# CAN_Bus_Controller_-_REV_1.net
KiCad netlist of a schematic drawn in EAGLE
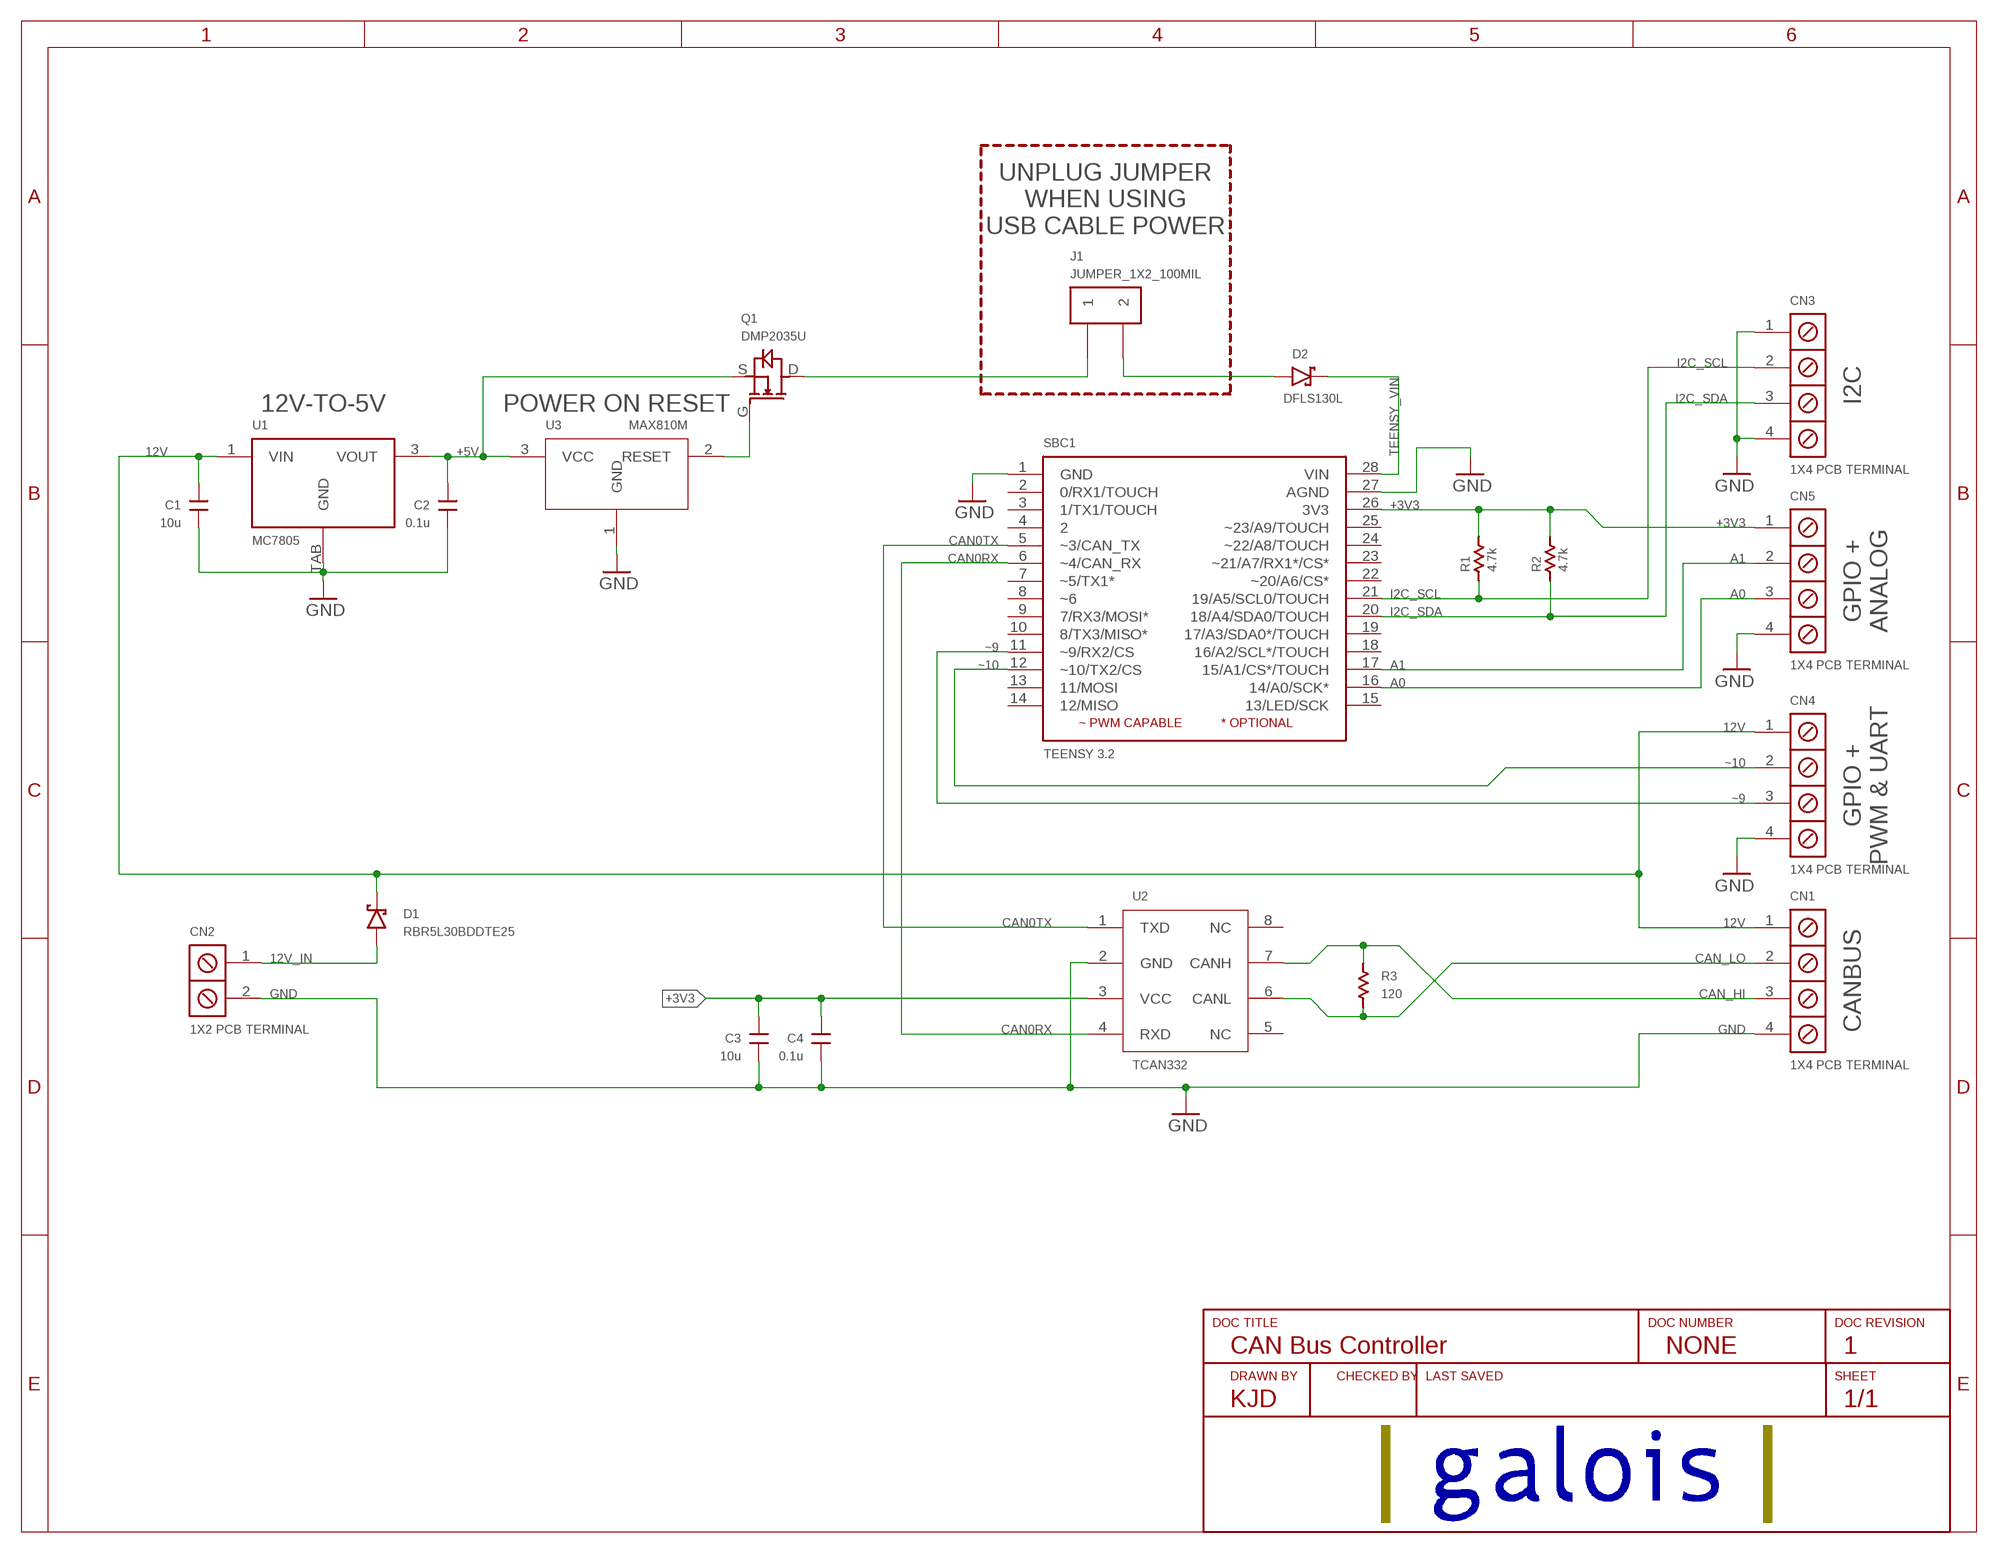
[diagram p0: schematic, sheet 1]

(export (version "E")
  (design (tool "Eeschema 10.0.6"))
  (components
    (comp (ref "C1")
      (value "10u")
      (footprint "eagle-import:EIA1206")
      (fields (field (name "MPN") "CL31A106KBHNNNE"))
      (libsource (lib "eagle-import") (part "C_SMDC1206"))
    )
    (comp (ref "C2")
      (value "0.1u")
      (footprint "eagle-import:EIA0603")
      (fields (field (name "MPN") "CL10B104KA8NNNC"))
      (libsource (lib "eagle-import") (part "C_SMDC0603"))
    )
    (comp (ref "C3")
      (value "10u")
      (footprint "eagle-import:EIA1206")
      (fields (field (name "MPN") "CL31A106KBHNNNE"))
      (libsource (lib "eagle-import") (part "C_SMDC1206"))
    )
    (comp (ref "C4")
      (value "0.1u")
      (footprint "eagle-import:EIA0603")
      (fields (field (name "MPN") "CL10B104KA8NNNC"))
      (libsource (lib "eagle-import") (part "C_SMDC0603"))
    )
    (comp (ref "CN1")
      (value "1X4 PCB TERMINAL")
      (footprint "eagle-import:PCB_TERM_3.5MM_PITCH_1X4")
      (fields (field (name "MPN") "1984633"))
      (libsource (lib "eagle-import") (part "1984633"))
    )
    (comp (ref "CN2")
      (value "1X2 PCB TERMINAL")
      (footprint "eagle-import:PCB_TERM_3.5MM_PITCH_1X2")
      (fields (field (name "MPN") "1984617"))
      (libsource (lib "eagle-import") (part "1984617"))
    )
    (comp (ref "CN3")
      (value "1X4 PCB TERMINAL")
      (footprint "eagle-import:PCB_TERM_3.5MM_PITCH_1X4")
      (fields (field (name "MPN") "1984633"))
      (libsource (lib "eagle-import") (part "1984633"))
    )
    (comp (ref "CN4")
      (value "1X4 PCB TERMINAL")
      (footprint "eagle-import:PCB_TERM_3.5MM_PITCH_1X4")
      (fields (field (name "MPN") "1984633"))
      (libsource (lib "eagle-import") (part "1984633"))
    )
    (comp (ref "CN5")
      (value "1X4 PCB TERMINAL")
      (footprint "eagle-import:PCB_TERM_3.5MM_PITCH_1X4")
      (fields (field (name "MPN") "1984633"))
      (libsource (lib "eagle-import") (part "1984633"))
    )
    (comp (ref "D1")
      (value "RBR5L30BDDTE25")
      (footprint "eagle-import:SMA")
      (fields (field (name "MPN") "RBR5L30BDDTE25"))
      (libsource (lib "eagle-import") (part "SCHOTTKYSMA"))
    )
    (comp (ref "D2")
      (value "DFLS130L")
      (footprint "eagle-import:POWERDI_123")
      (fields (field (name "MPN") "DFLS130L-7"))
      (libsource (lib "eagle-import") (part "SCHOTTKYPOWERDI_123"))
    )
    (comp (ref "J1")
      (value "JUMPER_1X2_100MIL")
      (footprint "eagle-import:1X2_100MIL_THRU")
      (fields (field (name "MPN") "QPC02SXGN-RC"))
      (libsource (lib "eagle-import") (part "1X2"))
    )
    (comp (ref "Q1")
      (value "DMP2035U")
      (footprint "eagle-import:SOT-23-3")
      (fields (field (name "MPN") "DMP2035U-7"))
      (libsource (lib "eagle-import") (part "DMP2035U"))
    )
    (comp (ref "R1")
      (value "4.7k")
      (footprint "eagle-import:EIA0603")
      (fields (field (name "MPN") "ERJ-3EKF4701V"))
      (libsource (lib "eagle-import") (part "R_SMDR0603"))
    )
    (comp (ref "R2")
      (value "4.7k")
      (footprint "eagle-import:EIA0603")
      (fields (field (name "MPN") "ERJ-3EKF4701V"))
      (libsource (lib "eagle-import") (part "R_SMDR0603"))
    )
    (comp (ref "R3")
      (value "120")
      (footprint "eagle-import:EIA1210")
      (fields (field (name "MPN") "AC1210FR-07120RL"))
      (libsource (lib "eagle-import") (part "R_SMDR1210"))
    )
    (comp (ref "SBC1")
      (value "TEENSY 3.2")
      (footprint "eagle-import:TEENSY3.2")
      (fields (field (name "MPN") "TEENSY32_PINS"))
      (libsource (lib "eagle-import") (part "TEENSY3.2"))
    )
    (comp (ref "U1")
      (value "MC7805")
      (footprint "eagle-import:DPAK-3")
      (fields (field (name "MPN") "MC7805CDTRKG"))
      (libsource (lib "eagle-import") (part "MC78XX"))
    )
    (comp (ref "U2")
      (value "TCAN332")
      (footprint "eagle-import:SOIC-8")
      (fields (field (name "MPN") "TCAN332DR"))
      (libsource (lib "eagle-import") (part "TCAN332_CANBUS_RXTX"))
    )
    (comp (ref "U3")
      (value "MAX810M")
      (footprint "eagle-import:SOT23-3")
      (fields (field (name "MPN") "MAX810MTRG"))
      (libsource (lib "eagle-import") (part "MAX809/810"))
    )
  )
  (nets
    (net (code "1") (name "+3V3") (class "Default")
      (node (ref "C3") (pin "P$2") (pinfunction "P$2_P$2") (pintype "passive"))
      (node (ref "C4") (pin "P$2") (pinfunction "P$2_P$2") (pintype "passive"))
      (node (ref "CN5") (pin "1") (pinfunction "1_1") (pintype "bidirectional"))
      (node (ref "R1") (pin "P$2") (pinfunction "P$2_P$2") (pintype "passive"))
      (node (ref "R2") (pin "P$2") (pinfunction "P$2_P$2") (pintype "passive"))
      (node (ref "SBC1") (pin "26") (pinfunction "3V3_26") (pintype "bidirectional"))
      (node (ref "U2") (pin "3") (pinfunction "VCC_3") (pintype "bidirectional"))
    )
    (net (code "2") (name "/+5V") (class "Default")
      (node (ref "C2") (pin "P$2") (pinfunction "P$2_P$2") (pintype "passive"))
      (node (ref "Q1") (pin "S") (pinfunction "S_S") (pintype "bidirectional"))
      (node (ref "U1") (pin "3") (pinfunction "VOUT_3") (pintype "bidirectional"))
      (node (ref "U3") (pin "3") (pinfunction "VCC_3") (pintype "bidirectional"))
    )
    (net (code "3") (name "/12V") (class "Default")
      (node (ref "C1") (pin "P$2") (pinfunction "P$2_P$2") (pintype "passive"))
      (node (ref "CN1") (pin "1") (pinfunction "1_1") (pintype "bidirectional"))
      (node (ref "CN4") (pin "1") (pinfunction "1_1") (pintype "bidirectional"))
      (node (ref "D1") (pin "C") (pinfunction "C_C") (pintype "bidirectional"))
      (node (ref "U1") (pin "1") (pinfunction "VIN_1") (pintype "bidirectional"))
    )
    (net (code "4") (name "/12V_IN") (class "Default")
      (node (ref "CN2") (pin "1") (pinfunction "1_1") (pintype "bidirectional"))
      (node (ref "D1") (pin "A") (pinfunction "A_A") (pintype "bidirectional"))
    )
    (net (code "5") (name "/A0") (class "Default")
      (node (ref "CN5") (pin "3") (pinfunction "3_3") (pintype "bidirectional"))
      (node (ref "SBC1") (pin "16") (pinfunction "14/A0/SCK*_16") (pintype "bidirectional"))
    )
    (net (code "6") (name "/A1") (class "Default")
      (node (ref "CN5") (pin "2") (pinfunction "2_2") (pintype "bidirectional"))
      (node (ref "SBC1") (pin "17") (pinfunction "15/A1/CS*/TOUCH_17") (pintype "bidirectional"))
    )
    (net (code "7") (name "/CAN0RX") (class "Default")
      (node (ref "SBC1") (pin "6") (pinfunction "~{4/CAN_RX}_6") (pintype "bidirectional"))
      (node (ref "U2") (pin "4") (pinfunction "RXD_4") (pintype "bidirectional"))
    )
    (net (code "8") (name "/CAN0TX") (class "Default")
      (node (ref "SBC1") (pin "5") (pinfunction "~{3/CAN_TX}_5") (pintype "bidirectional"))
      (node (ref "U2") (pin "1") (pinfunction "TXD_1") (pintype "bidirectional"))
    )
    (net (code "9") (name "/CAN_HI") (class "Default")
      (node (ref "CN1") (pin "3") (pinfunction "3_3") (pintype "bidirectional"))
      (node (ref "R3") (pin "P$2") (pinfunction "P$2_P$2") (pintype "passive"))
      (node (ref "U2") (pin "7") (pinfunction "CANH_7") (pintype "bidirectional"))
    )
    (net (code "10") (name "/CAN_LO") (class "Default")
      (node (ref "CN1") (pin "2") (pinfunction "2_2") (pintype "bidirectional"))
      (node (ref "R3") (pin "P$1") (pinfunction "P$1_P$1") (pintype "passive"))
      (node (ref "U2") (pin "6") (pinfunction "CANL_6") (pintype "bidirectional"))
    )
    (net (code "11") (name "/I2C_SCL") (class "Default")
      (node (ref "CN3") (pin "2") (pinfunction "2_2") (pintype "bidirectional"))
      (node (ref "R1") (pin "P$1") (pinfunction "P$1_P$1") (pintype "passive"))
      (node (ref "SBC1") (pin "21") (pinfunction "19/A5/SCL0/TOUCH_21") (pintype "bidirectional"))
    )
    (net (code "12") (name "/I2C_SDA") (class "Default")
      (node (ref "CN3") (pin "3") (pinfunction "3_3") (pintype "bidirectional"))
      (node (ref "R2") (pin "P$1") (pinfunction "P$1_P$1") (pintype "passive"))
      (node (ref "SBC1") (pin "20") (pinfunction "18/A4/SDA0/TOUCH_20") (pintype "bidirectional"))
    )
    (net (code "13") (name "/TEENSY_VIN") (class "Default")
      (node (ref "D2") (pin "C") (pinfunction "C_C") (pintype "bidirectional"))
      (node (ref "SBC1") (pin "28") (pinfunction "VIN_28") (pintype "bidirectional"))
    )
    (net (code "14") (name "/~{9}") (class "Default")
      (node (ref "CN4") (pin "3") (pinfunction "3_3") (pintype "bidirectional"))
      (node (ref "SBC1") (pin "11") (pinfunction "~{9/RX2/CS}_11") (pintype "bidirectional"))
    )
    (net (code "15") (name "/~{10}") (class "Default")
      (node (ref "CN4") (pin "2") (pinfunction "2_2") (pintype "bidirectional"))
      (node (ref "SBC1") (pin "12") (pinfunction "~{10/TX2/CS}_12") (pintype "bidirectional"))
    )
    (net (code "16") (name "GND") (class "Default")
      (node (ref "C1") (pin "P$1") (pinfunction "P$1_P$1") (pintype "passive"))
      (node (ref "C2") (pin "P$1") (pinfunction "P$1_P$1") (pintype "passive"))
      (node (ref "C3") (pin "P$1") (pinfunction "P$1_P$1") (pintype "passive"))
      (node (ref "C4") (pin "P$1") (pinfunction "P$1_P$1") (pintype "passive"))
      (node (ref "CN1") (pin "4") (pinfunction "4_4") (pintype "bidirectional"))
      (node (ref "CN2") (pin "2") (pinfunction "2_2") (pintype "bidirectional"))
      (node (ref "CN3") (pin "1") (pinfunction "1_1") (pintype "bidirectional"))
      (node (ref "CN3") (pin "4") (pinfunction "4_4") (pintype "bidirectional"))
      (node (ref "CN4") (pin "4") (pinfunction "4_4") (pintype "bidirectional"))
      (node (ref "CN5") (pin "4") (pinfunction "4_4") (pintype "bidirectional"))
      (node (ref "SBC1") (pin "1") (pinfunction "GND_1") (pintype "bidirectional"))
      (node (ref "SBC1") (pin "27") (pinfunction "AGND_27") (pintype "bidirectional"))
      (node (ref "U1") (pin "TAB") (pinfunction "GND_TAB") (pintype "bidirectional"))
      (node (ref "U2") (pin "2") (pinfunction "GND_2") (pintype "bidirectional"))
      (node (ref "U3") (pin "1") (pinfunction "GND_1") (pintype "bidirectional"))
    )
    (net (code "17") (name "Net-(D2-PadA)") (class "Default")
      (node (ref "D2") (pin "A") (pinfunction "A_A") (pintype "bidirectional"))
      (node (ref "J1") (pin "2") (pinfunction "2_2") (pintype "bidirectional"))
    )
    (net (code "18") (name "Net-(J1-Pad1)") (class "Default")
      (node (ref "J1") (pin "1") (pinfunction "1_1") (pintype "bidirectional"))
      (node (ref "Q1") (pin "D") (pinfunction "D_D") (pintype "bidirectional"))
    )
    (net (code "19") (name "Net-(U3-RESET)") (class "Default")
      (node (ref "Q1") (pin "G") (pinfunction "G_G") (pintype "bidirectional"))
      (node (ref "U3") (pin "2") (pinfunction "RESET_2") (pintype "bidirectional"))
    )
    (net (code "20") (name "unconnected-(SBC1-0{slash}RX1{slash}TOUCH-Pad2)") (class "Default")
      (node (ref "SBC1") (pin "2") (pinfunction "0/RX1/TOUCH_2") (pintype "bidirectional"))
    )
    (net (code "21") (name "unconnected-(SBC1-1{slash}TX1{slash}TOUCH-Pad3)") (class "Default")
      (node (ref "SBC1") (pin "3") (pinfunction "1/TX1/TOUCH_3") (pintype "bidirectional"))
    )
    (net (code "22") (name "unconnected-(SBC1-2-Pad4)") (class "Default")
      (node (ref "SBC1") (pin "4") (pinfunction "2_4") (pintype "bidirectional"))
    )
    (net (code "23") (name "unconnected-(SBC1-7{slash}RX3{slash}MOSI*-Pad9)") (class "Default")
      (node (ref "SBC1") (pin "9") (pinfunction "7/RX3/MOSI*_9") (pintype "bidirectional"))
    )
    (net (code "24") (name "unconnected-(SBC1-8{slash}TX3{slash}MISO*-Pad10)") (class "Default")
      (node (ref "SBC1") (pin "10") (pinfunction "8/TX3/MISO*_10") (pintype "bidirectional"))
    )
    (net (code "25") (name "unconnected-(SBC1-11{slash}MOSI-Pad13)") (class "Default")
      (node (ref "SBC1") (pin "13") (pinfunction "11/MOSI_13") (pintype "bidirectional"))
    )
    (net (code "26") (name "unconnected-(SBC1-12{slash}MISO-Pad14)") (class "Default")
      (node (ref "SBC1") (pin "14") (pinfunction "12/MISO_14") (pintype "bidirectional"))
    )
    (net (code "27") (name "unconnected-(SBC1-13{slash}LED{slash}SCK-Pad15)") (class "Default")
      (node (ref "SBC1") (pin "15") (pinfunction "13/LED/SCK_15") (pintype "bidirectional"))
    )
    (net (code "28") (name "unconnected-(SBC1-16{slash}A2{slash}SCL*{slash}TOUCH-Pad18)") (class "Default")
      (node (ref "SBC1") (pin "18") (pinfunction "16/A2/SCL*/TOUCH_18") (pintype "bidirectional"))
    )
    (net (code "29") (name "unconnected-(SBC1-17{slash}A3{slash}SDA0*{slash}TOUCH-Pad19)") (class "Default")
      (node (ref "SBC1") (pin "19") (pinfunction "17/A3/SDA0*/TOUCH_19") (pintype "bidirectional"))
    )
    (net (code "30") (name "unconnected-(SBC1-~{5{slash}TX1*}-Pad7)") (class "Default")
      (node (ref "SBC1") (pin "7") (pinfunction "~{5/TX1*}_7") (pintype "bidirectional"))
    )
    (net (code "31") (name "unconnected-(SBC1-~{6}-Pad8)") (class "Default")
      (node (ref "SBC1") (pin "8") (pinfunction "~{6}_8") (pintype "bidirectional"))
    )
    (net (code "32") (name "unconnected-(SBC1-~{20{slash}A6{slash}CS*}-Pad22)") (class "Default")
      (node (ref "SBC1") (pin "22") (pinfunction "~{20/A6/CS*}_22") (pintype "bidirectional"))
    )
    (net (code "33") (name "unconnected-(SBC1-~{21{slash}A7{slash}RX1*{slash}CS*}-Pad23)") (class "Default")
      (node (ref "SBC1") (pin "23") (pinfunction "~{21/A7/RX1*/CS*}_23") (pintype "bidirectional"))
    )
    (net (code "34") (name "unconnected-(SBC1-~{22{slash}A8{slash}TOUCH}-Pad24)") (class "Default")
      (node (ref "SBC1") (pin "24") (pinfunction "~{22/A8/TOUCH}_24") (pintype "bidirectional"))
    )
    (net (code "35") (name "unconnected-(SBC1-~{23{slash}A9{slash}TOUCH}-Pad25)") (class "Default")
      (node (ref "SBC1") (pin "25") (pinfunction "~{23/A9/TOUCH}_25") (pintype "bidirectional"))
    )
    (net (code "36") (name "unconnected-(U2-NC-Pad5)") (class "Default")
      (node (ref "U2") (pin "5") (pinfunction "NC_5") (pintype "bidirectional"))
    )
    (net (code "37") (name "unconnected-(U2-NC-Pad8)") (class "Default")
      (node (ref "U2") (pin "8") (pinfunction "NC_8") (pintype "bidirectional"))
    )
  )
)
